# 02_-_GSM.net
KiCad netlist of a schematic drawn in Altium Designer
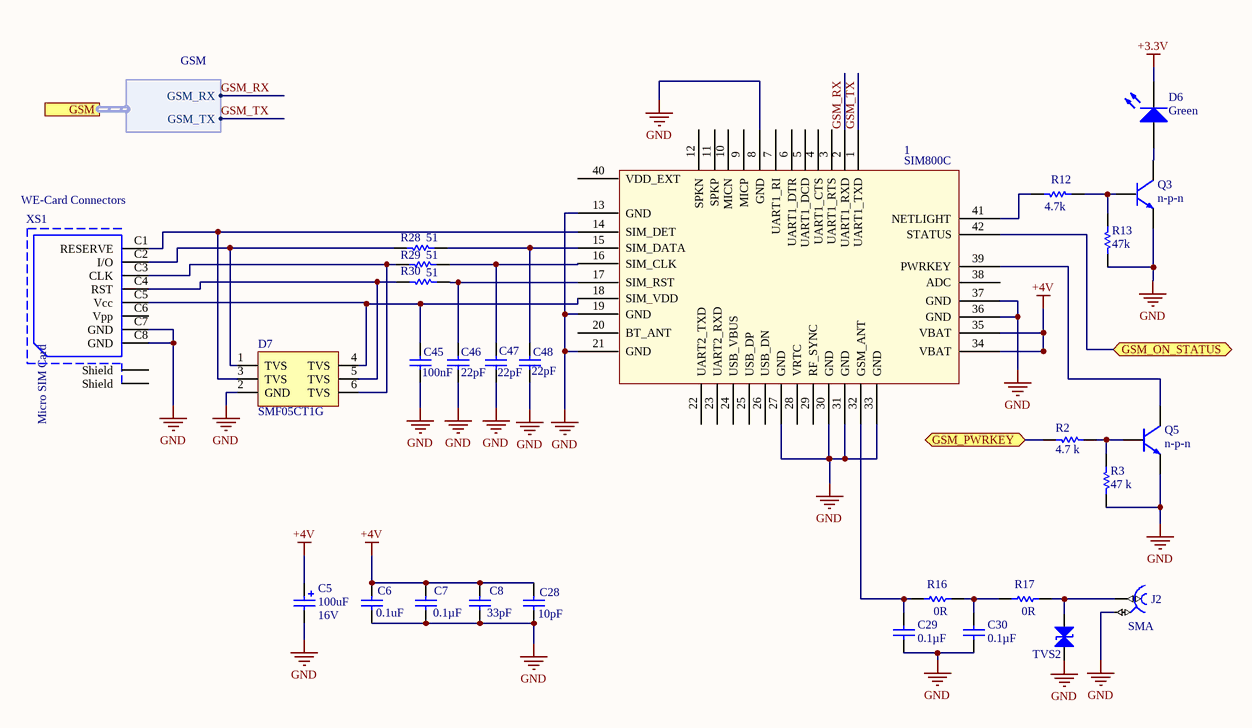
[diagram p0: [02] - GSM.SchDoc]

(export (version "E")
  (design (tool "Eeschema 10.0.6"))
  (components
    (comp (ref "1")
      (value "SIM800C")
      (description "GSM/GPS module")
      (libsource (lib "Blue Tractor-2021") (part "SIM800C"))
    )
    (comp (ref "C5")
      (value "Capacitor Polarized")
      (footprint "Tantalum 3216 A")
      (description "Tantalum Capacitor")
      (fields
        (field (name "MANUFACTURER") "Kemet")
        (field (name "MANUFACTURER PART NUMBER") "T491A106K016AT")
        (field (name "CAPACITANCE") "100uF")
        (field (name "VOLTAGE - RATED") "16V")
      )
      (libsource (lib "Altium_Library") (part "Capacitor Polarized"))
    )
    (comp (ref "C6")
      (value "Capacitor")
      (footprint "Cap 0603")
      (description "Chip Capacitor CER")
      (fields
        (field (name "MANUFACTURER") "Kemet")
        (field (name "MANUFACTURER PART NUMBER") "C0603C104K5RACTU")
        (field (name "CAPACITANCE") "0.1uF")
      )
      (libsource (lib "Altium_Library") (part "Capacitor"))
    )
    (comp (ref "C7")
      (value "Capacitor")
      (footprint "Cap 0603")
      (description "Chip Capacitor Nonpolar")
      (fields
        (field (name "MANUFACTURER") "Kemet")
        (field (name "MANUFACTURER PART NUMBER") "C0603C104K5RACTU")
        (field (name "CAPACITANCE") "0.1µF")
      )
      (libsource (lib "Altium_Library") (part "Capacitor"))
    )
    (comp (ref "C8")
      (value "Capacitor")
      (footprint "Cap 0603")
      (description "Chip Capacitor Nonpolar")
      (fields
        (field (name "MANUFACTURER") "Kemet")
        (field (name "MANUFACTURER PART NUMBER") "C0603C104K5RACTU")
        (field (name "CAPACITANCE") "33pF")
      )
      (libsource (lib "Altium_Library") (part "Capacitor"))
    )
    (comp (ref "C28")
      (value "Capacitor")
      (footprint "Cap 0603")
      (description "Chip Capacitor Nonpolar")
      (fields
        (field (name "MANUFACTURER") "Kemet")
        (field (name "MANUFACTURER PART NUMBER") "C0603C104K5RACTU")
        (field (name "CAPACITANCE") "10pF")
      )
      (libsource (lib "Altium_Library") (part "Capacitor"))
    )
    (comp (ref "C29")
      (value "Capacitor")
      (footprint "Cap 0603")
      (description "Chip Capacitor Nonpolar")
      (fields
        (field (name "MANUFACTURER") "Kemet")
        (field (name "MANUFACTURER PART NUMBER") "C0603C104K5RACTU")
        (field (name "CAPACITANCE") "0.1µF")
      )
      (libsource (lib "Altium_Library") (part "Capacitor"))
    )
    (comp (ref "C30")
      (value "Capacitor")
      (footprint "Cap 0603")
      (description "Chip Capacitor Nonpolar")
      (fields
        (field (name "MANUFACTURER") "Kemet")
        (field (name "MANUFACTURER PART NUMBER") "C0603C104K5RACTU")
        (field (name "CAPACITANCE") "0.1µF")
      )
      (libsource (lib "Altium_Library") (part "Capacitor"))
    )
    (comp (ref "C45")
      (value "Capacitor")
      (footprint "Cap 0603")
      (description "Chip Capacitor Nonpolar")
      (fields
        (field (name "MANUFACTURER") "Kemet")
        (field (name "MANUFACTURER PART NUMBER") "C0603C104K5RACTU")
        (field (name "CAPACITANCE") "100nF")
      )
      (libsource (lib "Altium_Library") (part "Capacitor"))
    )
    (comp (ref "C46")
      (value "Capacitor")
      (footprint "Cap 0603")
      (description "Chip Capacitor Nonpolar")
      (fields
        (field (name "MANUFACTURER") "Kemet")
        (field (name "MANUFACTURER PART NUMBER") "C0603C104K5RACTU")
        (field (name "CAPACITANCE") "22pF")
      )
      (libsource (lib "Altium_Library") (part "Capacitor"))
    )
    (comp (ref "C47")
      (value "Capacitor")
      (footprint "Cap 0603")
      (description "Chip Capacitor Nonpolar")
      (fields
        (field (name "MANUFACTURER") "Kemet")
        (field (name "MANUFACTURER PART NUMBER") "C0603C104K5RACTU")
        (field (name "CAPACITANCE") "22pF")
      )
      (libsource (lib "Altium_Library") (part "Capacitor"))
    )
    (comp (ref "C48")
      (value "Capacitor")
      (footprint "Cap 0603")
      (description "Chip Capacitor Nonpolar")
      (fields
        (field (name "MANUFACTURER") "Kemet")
        (field (name "MANUFACTURER PART NUMBER") "C0603C104K5RACTU")
        (field (name "CAPACITANCE") "22pF")
      )
      (libsource (lib "Altium_Library") (part "Capacitor"))
    )
    (comp (ref "D6")
      (value "LED")
      (footprint "Led 0805 green")
      (description "Led 0805")
      (fields
        (field (name "MANUFACTURER") "Vishay Lite-On")
        (field (name "MANUFACTURER PART NUMBER") "LTST-S220GKT")
        (field (name "COLOUR") "Green")
      )
      (libsource (lib "Altium_Library") (part "LED"))
    )
    (comp (ref "D7")
      (value "SMF05CT1G")
      (footprint "TSSOP6")
      (description "5-Line Transient Voltage  Suppressor Array")
      (fields (field (name "MANUFACTURER") "ON Semiconductor"))
      (libsource (lib "SIM68V") (part "SMF05CT1G"))
    )
    (comp (ref "J2")
      (value "SMA")
      (footprint "AMPHENOL_132134")
      (fields
        (field (name "MANUFACTURER") "TE Connectivity")
        (field (name "MANUFACTURER PART NUMBER") "5-1814832-1")
        (field (name "AUTHOR") "CERN DEM JLC")
      )
      (libsource (lib "Connectors") (part "Coax_1Female_1Shield"))
    )
    (comp (ref "Q3") (value "n-p-n") (libsource (lib "Blue Tractor-2021") (part "n-p-n transistor")))
    (comp (ref "Q5") (value "n-p-n") (libsource (lib "Blue Tractor-2021") (part "n-p-n transistor")))
    (comp (ref "R2")
      (value "Res1")
      (footprint "Res-0603")
      (description "Chip Resistor")
      (fields
        (field (name "MANUFACTURER") "Panasonic")
        (field (name "MANUFACTURER PART NUMBER") "ERJ-3GEYJ103V")
        (field (name "RESISTANCE") "4.7 k")
      )
      (libsource (lib "Altium_Library") (part "Res1"))
    )
    (comp (ref "R3")
      (value "Res1")
      (footprint "Res-0603")
      (description "Chip Resistor")
      (fields
        (field (name "MANUFACTURER") "Panasonic")
        (field (name "MANUFACTURER PART NUMBER") "ERJ-3GEYJ103V")
        (field (name "RESISTANCE") "47 k")
      )
      (libsource (lib "Altium_Library") (part "Res1"))
    )
    (comp (ref "R12")
      (value "Res1")
      (footprint "Res-0603")
      (description "Chip Resistor")
      (fields
        (field (name "MANUFACTURER") "Panasonic")
        (field (name "MANUFACTURER PART NUMBER") "ERJ-3EKF3300V")
        (field (name "RESISTANCE") "4.7k")
      )
      (libsource (lib "Altium_Library") (part "Res1"))
    )
    (comp (ref "R13")
      (value "Res1")
      (footprint "Res-0603")
      (description "Chip Resistor")
      (fields
        (field (name "MANUFACTURER") "Panasonic")
        (field (name "MANUFACTURER PART NUMBER") "ERJ-3EKF3300V")
        (field (name "RESISTANCE") "47k")
      )
      (libsource (lib "Altium_Library") (part "Res1"))
    )
    (comp (ref "R16")
      (value "Res1")
      (footprint "Res-0603")
      (description "Chip Resistor")
      (fields
        (field (name "MANUFACTURER") "Panasonic")
        (field (name "MANUFACTURER PART NUMBER") "ERJ-3GEY0R00V")
        (field (name "RESISTANCE") "0R")
      )
      (libsource (lib "Altium_Library") (part "Res1"))
    )
    (comp (ref "R17")
      (value "Res1")
      (footprint "Res-0603")
      (description "Chip Resistor")
      (fields
        (field (name "MANUFACTURER") "Panasonic")
        (field (name "MANUFACTURER PART NUMBER") "ERJ-3GEY0R00V")
        (field (name "RESISTANCE") "0R")
      )
      (libsource (lib "Altium_Library") (part "Res1"))
    )
    (comp (ref "R28")
      (value "Res1")
      (footprint "Res-0603")
      (description "Chip Resistor")
      (fields
        (field (name "MANUFACTURER") "Panasonic")
        (field (name "MANUFACTURER PART NUMBER") "ERJ-3EKF3300V")
        (field (name "RESISTANCE") "51")
      )
      (libsource (lib "Altium_Library") (part "Res1"))
    )
    (comp (ref "R29")
      (value "Res1")
      (footprint "Res-0603")
      (description "Chip Resistor")
      (fields
        (field (name "MANUFACTURER") "Panasonic")
        (field (name "MANUFACTURER PART NUMBER") "ERJ-3EKF3300V")
        (field (name "RESISTANCE") "51")
      )
      (libsource (lib "Altium_Library") (part "Res1"))
    )
    (comp (ref "R30")
      (value "Res1")
      (footprint "Res-0603")
      (description "Chip Resistor")
      (fields
        (field (name "MANUFACTURER") "Panasonic")
        (field (name "MANUFACTURER PART NUMBER") "ERJ-3EKF3300V")
        (field (name "RESISTANCE") "51")
      )
      (libsource (lib "Altium_Library") (part "Res1"))
    )
    (comp (ref "TVS2")
      (value "LXE15AAA1-153")
      (libsource (lib "Blue Tractor-2021") (part "TVS-LXE15AAA1-153"))
    )
    (comp (ref "XS1")
      (value "WE-Card Connectors")
      (footprint "693022010811")
      (description "WR-CRD Micro SIM_Hinge_8 pins")
      (fields
        (field (name "MANUFACTURER") "Würth Elektronik eiSos GmbH")
        (field (name "PARTNO") "693022010811")
        (field (name "CREATED BY") "Karrer Zheng")
      )
      (libsource (lib "Blue Tractor-2021") (part "WE-Card Connectors 693022010811"))
    )
  )
  (nets
    (net (code "2") (name "+3.3V") (class "Default")
      (node (ref "D6") (pin "2") (pinfunction "K_2") (pintype "passive"))
    )
    (net (code "3") (name "+4V") (class "Default")
      (node (ref "1") (pin "34") (pinfunction "VBAT_34") (pintype "power_in"))
      (node (ref "1") (pin "35") (pinfunction "VBAT_35") (pintype "power_in"))
      (node (ref "C28") (pin "2") (pinfunction "2_2") (pintype "passive"))
      (node (ref "C5") (pin "1") (pinfunction "1_1") (pintype "passive"))
      (node (ref "C6") (pin "2") (pinfunction "2_2") (pintype "passive"))
      (node (ref "C7") (pin "2") (pinfunction "2_2") (pintype "passive"))
      (node (ref "C8") (pin "2") (pinfunction "2_2") (pintype "passive"))
    )
    (net (code "4") (name "/GSM_ON_STATUS") (class "Default")
      (node (ref "1") (pin "42") (pinfunction "STATUS_42") (pintype "power_in"))
    )
    (net (code "5") (name "/GSM_PWRKEY") (class "Default")
      (node (ref "R2") (pin "2") (pinfunction "2_2") (pintype "passive"))
    )
    (net (code "6") (name "/GSM_RX") (class "Default")
      (node (ref "1") (pin "2") (pinfunction "UART1_RXD_2") (pintype "power_in"))
    )
    (net (code "7") (name "/GSM_TX") (class "Default")
      (node (ref "1") (pin "1") (pinfunction "UART1_TXD_1") (pintype "power_in"))
    )
    (net (code "9") (name "GND") (class "Default")
      (node (ref "1") (pin "13") (pinfunction "GND_13") (pintype "passive"))
      (node (ref "1") (pin "19") (pinfunction "GND_19") (pintype "passive"))
      (node (ref "1") (pin "21") (pinfunction "GND_21") (pintype "passive"))
      (node (ref "1") (pin "27") (pinfunction "GND_27") (pintype "passive"))
      (node (ref "1") (pin "30") (pinfunction "GND_30") (pintype "passive"))
      (node (ref "1") (pin "31") (pinfunction "GND_31") (pintype "passive"))
      (node (ref "1") (pin "33") (pinfunction "GND_33") (pintype "power_in"))
      (node (ref "1") (pin "36") (pinfunction "GND_36") (pintype "power_in"))
      (node (ref "1") (pin "37") (pinfunction "GND_37") (pintype "power_in"))
      (node (ref "1") (pin "8") (pinfunction "GND_8") (pintype "passive"))
      (node (ref "C28") (pin "1") (pinfunction "1_1") (pintype "passive"))
      (node (ref "C29") (pin "1") (pinfunction "1_1") (pintype "passive"))
      (node (ref "C30") (pin "1") (pinfunction "1_1") (pintype "passive"))
      (node (ref "C45") (pin "1") (pinfunction "1_1") (pintype "passive"))
      (node (ref "C46") (pin "1") (pinfunction "1_1") (pintype "passive"))
      (node (ref "C47") (pin "1") (pinfunction "1_1") (pintype "passive"))
      (node (ref "C48") (pin "1") (pinfunction "1_1") (pintype "passive"))
      (node (ref "C5") (pin "2") (pinfunction "2_2") (pintype "passive"))
      (node (ref "C6") (pin "1") (pinfunction "1_1") (pintype "passive"))
      (node (ref "C7") (pin "1") (pinfunction "1_1") (pintype "passive"))
      (node (ref "C8") (pin "1") (pinfunction "1_1") (pintype "passive"))
      (node (ref "D7") (pin "2") (pinfunction "GND_2") (pintype "passive"))
      (node (ref "J2") (pin "2") (pinfunction "2_2") (pintype "bidirectional"))
      (node (ref "Q3") (pin "17") (pinfunction "17_17") (pintype "passive"))
      (node (ref "Q5") (pin "17") (pinfunction "17_17") (pintype "passive"))
      (node (ref "R13") (pin "1") (pinfunction "1_1") (pintype "passive"))
      (node (ref "R3") (pin "1") (pinfunction "1_1") (pintype "passive"))
      (node (ref "TVS2") (pin "16") (pinfunction "16_16") (pintype "passive"))
      (node (ref "XS1") (pin "C7") (pinfunction "GND_C7") (pintype "passive"))
      (node (ref "XS1") (pin "C8") (pinfunction "GND_C8") (pintype "passive"))
    )
    (net (code "10") (name "Net-(1-GSM_ANT)") (class "Default")
      (node (ref "1") (pin "32") (pinfunction "GSM_ANT_32") (pintype "passive"))
      (node (ref "C29") (pin "2") (pinfunction "2_2") (pintype "passive"))
      (node (ref "R16") (pin "2") (pinfunction "2_2") (pintype "passive"))
    )
    (net (code "11") (name "Net-(1-NETLIGHT)") (class "Default")
      (node (ref "1") (pin "41") (pinfunction "NETLIGHT_41") (pintype "power_in"))
      (node (ref "R12") (pin "1") (pinfunction "1_1") (pintype "passive"))
    )
    (net (code "12") (name "Net-(1-PWRKEY)") (class "Default")
      (node (ref "1") (pin "39") (pinfunction "PWRKEY_39") (pintype "power_in"))
      (node (ref "Q5") (pin "16") (pinfunction "16_16") (pintype "passive"))
    )
    (net (code "13") (name "Net-(1-SIM_CLK)") (class "Default")
      (node (ref "1") (pin "16") (pinfunction "SIM_CLK_16") (pintype "passive"))
      (node (ref "C47") (pin "2") (pinfunction "2_2") (pintype "passive"))
      (node (ref "R29") (pin "1") (pinfunction "1_1") (pintype "passive"))
    )
    (net (code "14") (name "Net-(1-SIM_DATA)") (class "Default")
      (node (ref "1") (pin "15") (pinfunction "SIM_DATA_15") (pintype "passive"))
      (node (ref "C48") (pin "2") (pinfunction "2_2") (pintype "passive"))
      (node (ref "R28") (pin "1") (pinfunction "1_1") (pintype "passive"))
    )
    (net (code "15") (name "Net-(1-SIM_DET)") (class "Default")
      (node (ref "1") (pin "14") (pinfunction "SIM_DET_14") (pintype "passive"))
      (node (ref "D7") (pin "3") (pinfunction "TVS_3") (pintype "passive"))
      (node (ref "XS1") (pin "C1") (pinfunction "RESERVE_C1") (pintype "passive"))
    )
    (net (code "16") (name "Net-(1-SIM_RST)") (class "Default")
      (node (ref "1") (pin "17") (pinfunction "SIM_RST_17") (pintype "passive"))
      (node (ref "C46") (pin "2") (pinfunction "2_2") (pintype "passive"))
      (node (ref "R30") (pin "1") (pinfunction "1_1") (pintype "passive"))
    )
    (net (code "17") (name "Net-(1-SIM_VDD)") (class "Default")
      (node (ref "1") (pin "18") (pinfunction "SIM_VDD_18") (pintype "passive"))
      (node (ref "C45") (pin "2") (pinfunction "2_2") (pintype "passive"))
      (node (ref "D7") (pin "4") (pinfunction "TVS_4") (pintype "passive"))
      (node (ref "XS1") (pin "C5") (pinfunction "Vcc_C5") (pintype "passive"))
    )
    (net (code "18") (name "Net-(C30-Pad2)") (class "Default")
      (node (ref "C30") (pin "2") (pinfunction "2_2") (pintype "passive"))
      (node (ref "R16") (pin "1") (pinfunction "1_1") (pintype "passive"))
      (node (ref "R17") (pin "2") (pinfunction "2_2") (pintype "passive"))
    )
    (net (code "19") (name "Net-(D6-A)") (class "Default")
      (node (ref "D6") (pin "1") (pinfunction "A_1") (pintype "passive"))
      (node (ref "Q3") (pin "16") (pinfunction "16_16") (pintype "passive"))
    )
    (net (code "20") (name "Net-(J2-Pad1)") (class "Default")
      (node (ref "J2") (pin "1") (pinfunction "1_1") (pintype "bidirectional"))
      (node (ref "R17") (pin "1") (pinfunction "1_1") (pintype "passive"))
      (node (ref "TVS2") (pin "16") (pinfunction "16_16") (pintype "passive"))
    )
    (net (code "21") (name "Net-(Q3-PG)") (class "Default")
      (node (ref "Q3") (pin "15") (pinfunction "PG_15") (pintype "passive"))
      (node (ref "R12") (pin "2") (pinfunction "2_2") (pintype "passive"))
      (node (ref "R13") (pin "2") (pinfunction "2_2") (pintype "passive"))
    )
    (net (code "22") (name "Net-(Q5-PG)") (class "Default")
      (node (ref "Q5") (pin "15") (pinfunction "PG_15") (pintype "passive"))
      (node (ref "R2") (pin "1") (pinfunction "1_1") (pintype "passive"))
      (node (ref "R3") (pin "2") (pinfunction "2_2") (pintype "passive"))
    )
    (net (code "23") (name "Net-(XS1-CLK)") (class "Default")
      (node (ref "D7") (pin "6") (pinfunction "TVS_6") (pintype "passive"))
      (node (ref "R29") (pin "2") (pinfunction "2_2") (pintype "passive"))
      (node (ref "XS1") (pin "C3") (pinfunction "CLK_C3") (pintype "passive"))
    )
    (net (code "24") (name "Net-(XS1-I{slash}O)") (class "Default")
      (node (ref "D7") (pin "1") (pinfunction "TVS_1") (pintype "passive"))
      (node (ref "R28") (pin "2") (pinfunction "2_2") (pintype "passive"))
      (node (ref "XS1") (pin "C2") (pinfunction "I/O_C2") (pintype "passive"))
    )
    (net (code "25") (name "Net-(XS1-RST)") (class "Default")
      (node (ref "D7") (pin "5") (pinfunction "TVS_5") (pintype "passive"))
      (node (ref "R30") (pin "2") (pinfunction "2_2") (pintype "passive"))
      (node (ref "XS1") (pin "C4") (pinfunction "RST_C4") (pintype "passive"))
    )
    (net (code "26") (name "unconnected-(1-ADC-Pad38)") (class "Default")
      (node (ref "1") (pin "38") (pinfunction "ADC_38") (pintype "power_in"))
    )
    (net (code "27") (name "unconnected-(1-BT_ANT-Pad20)") (class "Default")
      (node (ref "1") (pin "20") (pinfunction "BT_ANT_20") (pintype "passive"))
    )
    (net (code "28") (name "unconnected-(1-MICN-Pad10)") (class "Default")
      (node (ref "1") (pin "10") (pinfunction "MICN_10") (pintype "passive"))
    )
    (net (code "29") (name "unconnected-(1-MICP-Pad9)") (class "Default")
      (node (ref "1") (pin "9") (pinfunction "MICP_9") (pintype "passive"))
    )
    (net (code "30") (name "unconnected-(1-RF_SYNC-Pad29)") (class "Default")
      (node (ref "1") (pin "29") (pinfunction "RF_SYNC_29") (pintype "passive"))
    )
    (net (code "31") (name "unconnected-(1-SPKN-Pad12)") (class "Default")
      (node (ref "1") (pin "12") (pinfunction "SPKN_12") (pintype "passive"))
    )
    (net (code "32") (name "unconnected-(1-SPKP-Pad11)") (class "Default")
      (node (ref "1") (pin "11") (pinfunction "SPKP_11") (pintype "passive"))
    )
    (net (code "33") (name "unconnected-(1-UART1_CTS-Pad4)") (class "Default")
      (node (ref "1") (pin "4") (pinfunction "UART1_CTS_4") (pintype "passive"))
    )
    (net (code "34") (name "unconnected-(1-UART1_DCD-Pad5)") (class "Default")
      (node (ref "1") (pin "5") (pinfunction "UART1_DCD_5") (pintype "passive"))
    )
    (net (code "35") (name "unconnected-(1-UART1_DTR-Pad6)") (class "Default")
      (node (ref "1") (pin "6") (pinfunction "UART1_DTR_6") (pintype "passive"))
    )
    (net (code "36") (name "unconnected-(1-UART1_RI-Pad7)") (class "Default")
      (node (ref "1") (pin "7") (pinfunction "UART1_RI_7") (pintype "passive"))
    )
    (net (code "37") (name "unconnected-(1-UART1_RTS-Pad3)") (class "Default")
      (node (ref "1") (pin "3") (pinfunction "UART1_RTS_3") (pintype "power_in"))
    )
    (net (code "38") (name "unconnected-(1-UART2_RXD-Pad23)") (class "Default")
      (node (ref "1") (pin "23") (pinfunction "UART2_RXD_23") (pintype "passive"))
    )
    (net (code "39") (name "unconnected-(1-UART2_TXD-Pad22)") (class "Default")
      (node (ref "1") (pin "22") (pinfunction "UART2_TXD_22") (pintype "passive"))
    )
    (net (code "40") (name "unconnected-(1-USB_DN-Pad26)") (class "Default")
      (node (ref "1") (pin "26") (pinfunction "USB_DN_26") (pintype "passive"))
    )
    (net (code "41") (name "unconnected-(1-USB_DP-Pad25)") (class "Default")
      (node (ref "1") (pin "25") (pinfunction "USB_DP_25") (pintype "passive"))
    )
    (net (code "42") (name "unconnected-(1-USB_VBUS-Pad24)") (class "Default")
      (node (ref "1") (pin "24") (pinfunction "USB_VBUS_24") (pintype "passive"))
    )
    (net (code "43") (name "unconnected-(1-VDD_EXT-Pad40)") (class "Default")
      (node (ref "1") (pin "40") (pinfunction "VDD_EXT_40") (pintype "power_in"))
    )
    (net (code "44") (name "unconnected-(1-VRTC-Pad28)") (class "Default")
      (node (ref "1") (pin "28") (pinfunction "VRTC_28") (pintype "passive"))
    )
    (net (code "45") (name "unconnected-(XS1-Shield-PadZ1)") (class "Default")
      (node (ref "XS1") (pin "Z1") (pinfunction "Shield_Z1") (pintype "passive"))
    )
    (net (code "46") (name "unconnected-(XS1-Shield-PadZ2)") (class "Default")
      (node (ref "XS1") (pin "Z2") (pinfunction "Shield_Z2") (pintype "passive"))
    )
    (net (code "47") (name "unconnected-(XS1-Vpp-PadC6)") (class "Default")
      (node (ref "XS1") (pin "C6") (pinfunction "Vpp_C6") (pintype "passive"))
    )
  )
)
